# MCU.net
KiCad netlist of a schematic drawn in Altium Designer
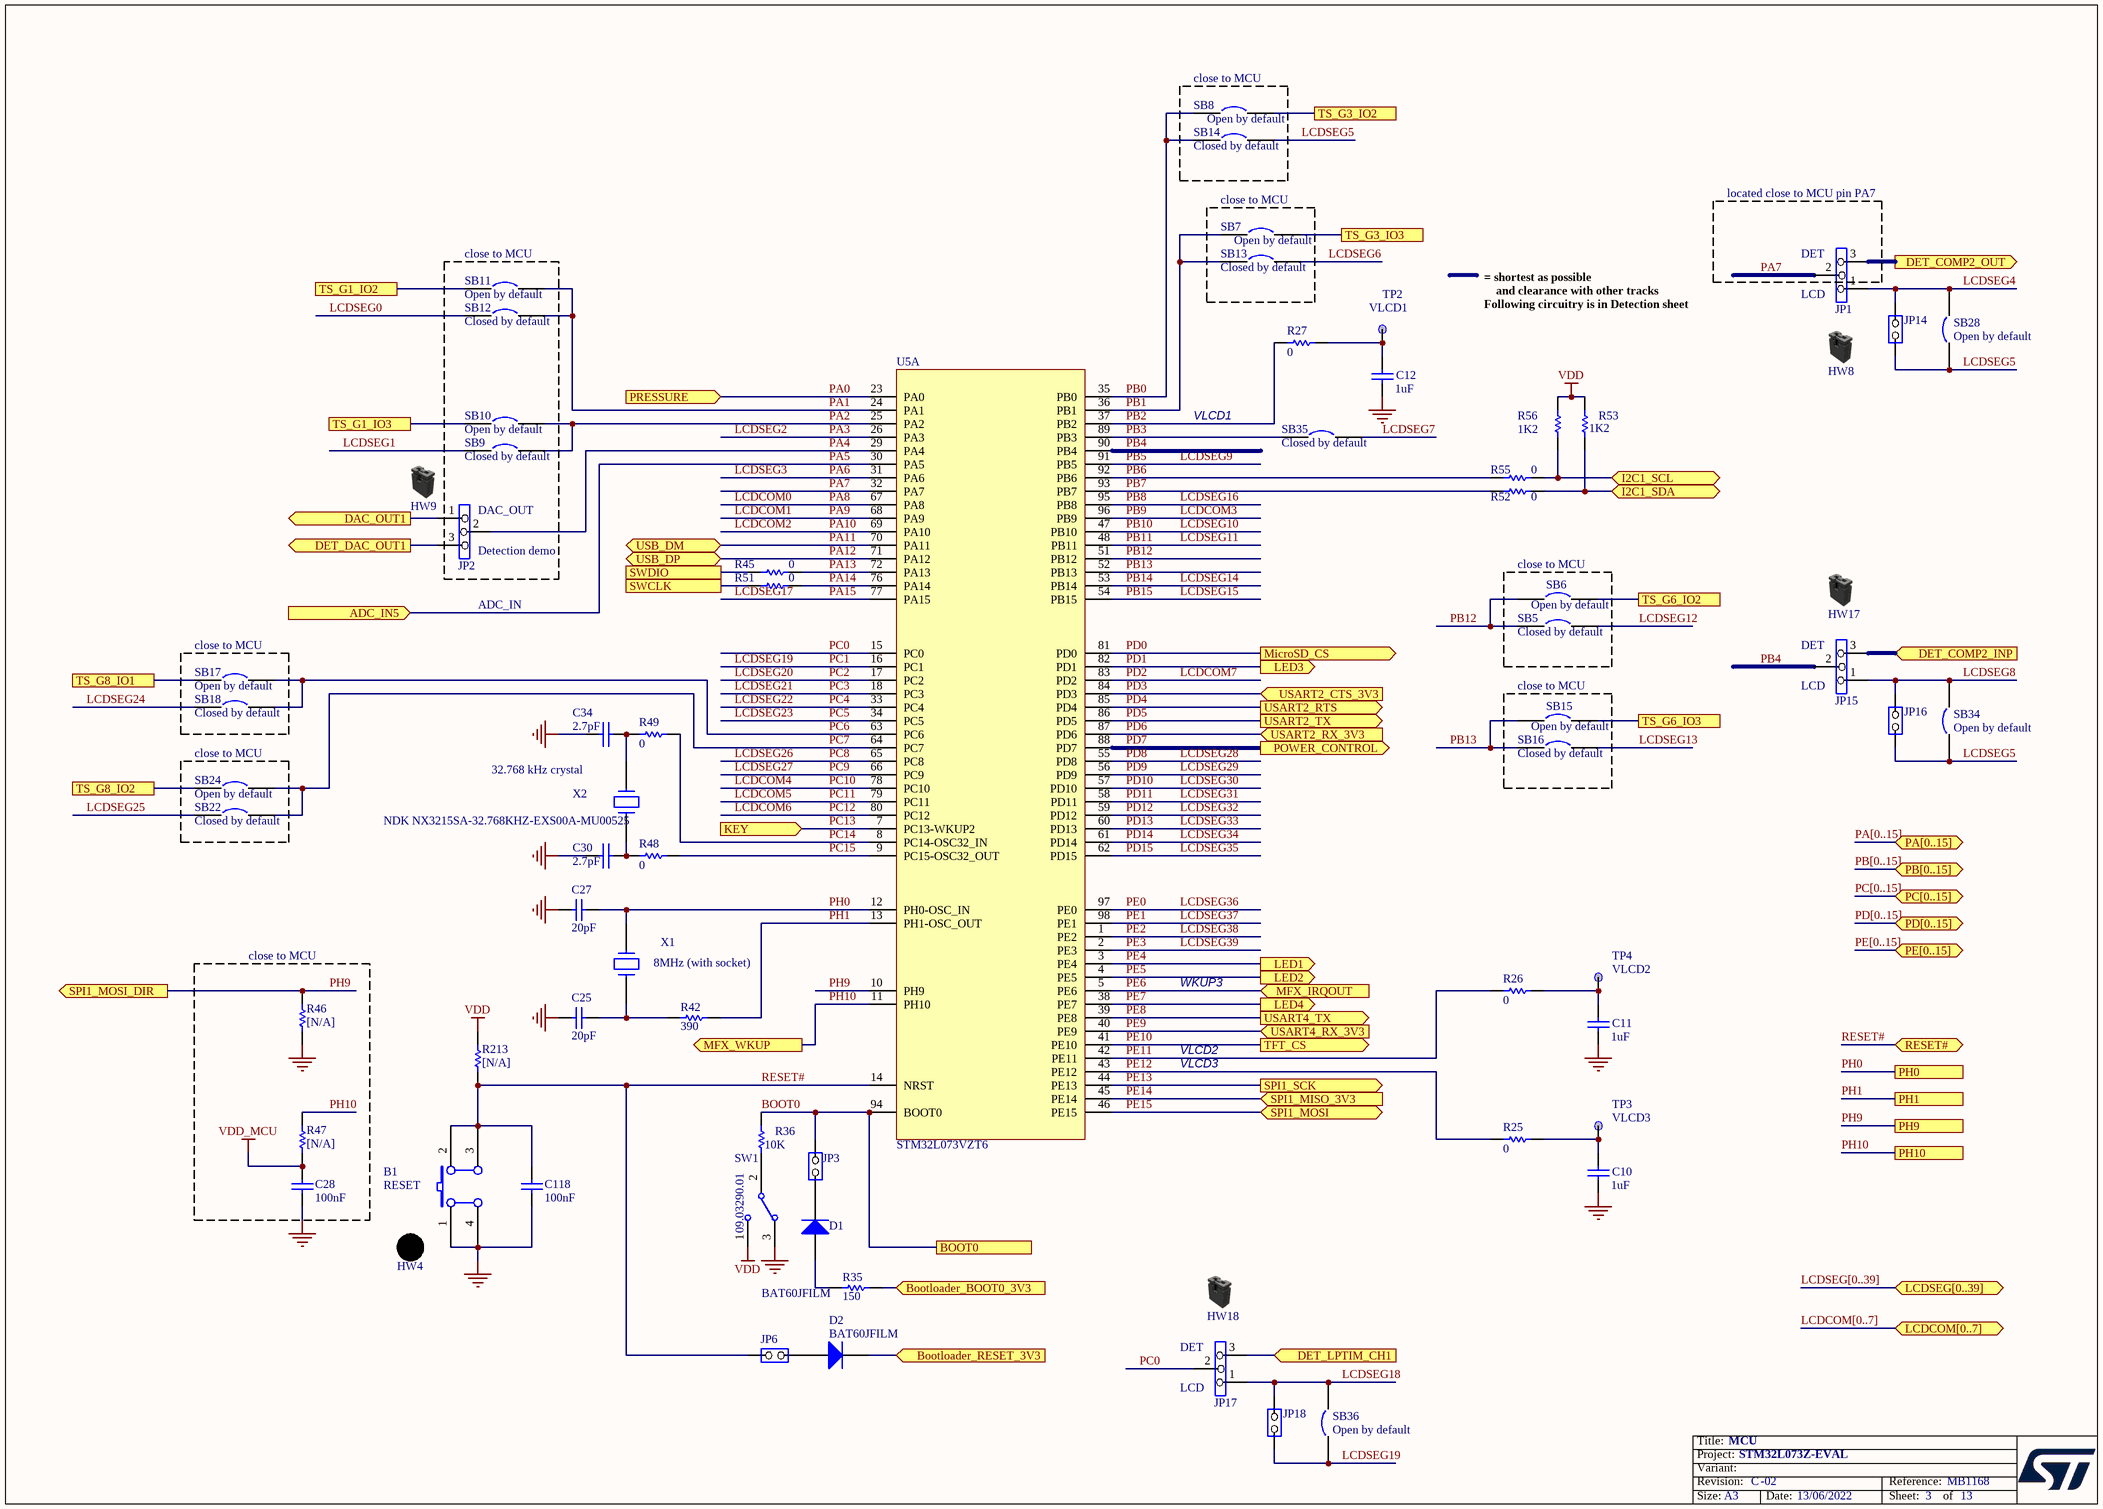
[diagram p0: MCU.SchDoc]

(export (version "E")
  (design (tool "Eeschema 10.0.6"))
  (components
    (comp (ref "B1")
      (value "RESET")
      (footprint "PB10")
      (description "SE PUSHBUTTON")
      (libsource (lib "Documents") (part "SW PUSHBUTTON"))
    )
    (comp (ref "C10")
      (value "1uF")
      (footprint "0603C")
      (description "Capacitor")
      (fields (field (name "PUBLISHER") "Altium Limited"))
      (libsource (lib "Miscellaneous Devices") (part "CAP"))
    )
    (comp (ref "C11")
      (value "1uF")
      (footprint "0603C")
      (description "Capacitor")
      (fields (field (name "PUBLISHER") "Altium Limited"))
      (libsource (lib "Miscellaneous Devices") (part "CAP"))
    )
    (comp (ref "C12")
      (value "1uF")
      (footprint "0603C")
      (description "Capacitor")
      (fields (field (name "PUBLISHER") "Altium Limited"))
      (libsource (lib "Miscellaneous Devices") (part "CAP"))
    )
    (comp (ref "C25")
      (value "20pF")
      (footprint "0402C")
      (description "Capacitor")
      (fields (field (name "PUBLISHER") "Altium Limited"))
      (libsource (lib "Miscellaneous Devices") (part "CAP"))
    )
    (comp (ref "C27")
      (value "20pF")
      (footprint "0402C")
      (description "Capacitor")
      (fields (field (name "PUBLISHER") "Altium Limited"))
      (libsource (lib "Miscellaneous Devices") (part "CAP"))
    )
    (comp (ref "C28")
      (value "100nF")
      (footprint "0402C")
      (description "Capacitor")
      (fields (field (name "PUBLISHER") "Altium Limited"))
      (libsource (lib "Miscellaneous Devices") (part "CAP"))
    )
    (comp (ref "C30")
      (value "2.7pF")
      (footprint "0603C")
      (description "Capacitor")
      (libsource (lib "*") (part "CAP"))
    )
    (comp (ref "C34")
      (value "2.7pF")
      (footprint "0603C")
      (description "Capacitor")
      (libsource (lib "*") (part "CAP"))
    )
    (comp (ref "C118")
      (value "100nF")
      (footprint "0402C")
      (description "Capacitor")
      (fields (field (name "PUBLISHER") "Altium Limited"))
      (libsource (lib "Miscellaneous Devices") (part "CAP"))
    )
    (comp (ref "D1")
      (value "BAT60JFILM")
      (footprint "SOD-323")
      (description "Default Diode")
      (fields (field (name "PUBLISHER") "Altium Limited"))
      (libsource (lib "Miscellaneous Devices") (part "Diode"))
    )
    (comp (ref "D2")
      (value "BAT60JFILM")
      (footprint "SOD-323")
      (description "Default Diode")
      (fields (field (name "PUBLISHER") "Altium Limited"))
      (libsource (lib "Miscellaneous Devices") (part "Diode"))
    )
    (comp (ref "HW4") (value "BUTTON_HAT_BLACK") (libsource (lib "MB1168") (part "BUTTON_HAT_BLACK")))
    (comp (ref "HW8") (value "Shunt Black 2.54mm") (libsource (lib "MB1168") (part "Shunt Black 2.54mm")))
    (comp (ref "HW9") (value "Shunt Black 2.54mm") (libsource (lib "MB1168") (part "Shunt Black 2.54mm")))
    (comp (ref "HW17") (value "Shunt Black 2.54mm") (libsource (lib "MB1168") (part "Shunt Black 2.54mm")))
    (comp (ref "HW18") (value "Shunt Black 2.54mm") (libsource (lib "MB1168") (part "Shunt Black 2.54mm")))
    (comp (ref "JP1") (value "~") (footprint "SIP3") (libsource (lib "STR910_SCHLIB") (part "Jumper3")))
    (comp (ref "JP2") (value "~") (footprint "SIP3") (libsource (lib "STR910_SCHLIB") (part "Jumper3")))
    (comp (ref "JP3") (value "~") (footprint "SIP2") (libsource (lib "*") (part "JP2")))
    (comp (ref "JP6") (value "~") (footprint "SIP2") (libsource (lib "*") (part "JP2")))
    (comp (ref "JP14") (value "~") (footprint "SIP2") (libsource (lib "*") (part "JP2")))
    (comp (ref "JP15") (value "~") (footprint "SIP3") (libsource (lib "STR910_SCHLIB") (part "Jumper3")))
    (comp (ref "JP16") (value "~") (footprint "SIP2") (libsource (lib "*") (part "JP2")))
    (comp (ref "JP17") (value "~") (footprint "SIP3") (libsource (lib "STR910_SCHLIB") (part "Jumper3")))
    (comp (ref "JP18") (value "~") (footprint "SIP2") (libsource (lib "*") (part "JP2")))
    (comp (ref "R25")
      (value "0")
      (footprint "0603R")
      (description "Resistor")
      (fields (field (name "PUBLISHER") "Altium Limited"))
      (libsource (lib "Miscellaneous Devices") (part "Res1"))
    )
    (comp (ref "R26")
      (value "0")
      (footprint "0603R")
      (description "Resistor")
      (fields (field (name "PUBLISHER") "Altium Limited"))
      (libsource (lib "Miscellaneous Devices") (part "Res1"))
    )
    (comp (ref "R27")
      (value "0")
      (footprint "0603R")
      (description "Resistor")
      (fields (field (name "PUBLISHER") "Altium Limited"))
      (libsource (lib "Miscellaneous Devices") (part "Res1"))
    )
    (comp (ref "R35")
      (value "150")
      (footprint "0402R")
      (description "Resistor")
      (fields (field (name "PUBLISHER") "Altium Limited"))
      (libsource (lib "Miscellaneous Devices") (part "res1"))
    )
    (comp (ref "R36")
      (value "10K")
      (footprint "0402R")
      (description "Resistor")
      (fields (field (name "PUBLISHER") "Altium Limited"))
      (libsource (lib "Miscellaneous Devices") (part "res1"))
    )
    (comp (ref "R42")
      (value "390")
      (footprint "0603R")
      (description "Resistor")
      (fields (field (name "PUBLISHER") "Altium Limited"))
      (libsource (lib "Miscellaneous Devices") (part "Res1"))
    )
    (comp (ref "R45")
      (value "0")
      (footprint "0603R")
      (description "Resistor")
      (fields (field (name "PUBLISHER") "Altium Limited"))
      (libsource (lib "Miscellaneous Devices") (part "Res1"))
    )
    (comp (ref "R46")
      (value "[N/A]")
      (footprint "0603R")
      (description "Resistor")
      (fields (field (name "PUBLISHER") "Altium Limited"))
      (libsource (lib "Miscellaneous Devices") (part "res1"))
    )
    (comp (ref "R47")
      (value "[N/A]")
      (footprint "0603R")
      (description "Resistor")
      (fields (field (name "PUBLISHER") "Altium Limited"))
      (libsource (lib "Miscellaneous Devices") (part "res1"))
    )
    (comp (ref "R48")
      (value "0")
      (footprint "0603R")
      (description "Resistor")
      (fields (field (name "PUBLISHER") "Altium Limited"))
      (libsource (lib "") (part "Res1_1"))
    )
    (comp (ref "R49")
      (value "0")
      (footprint "0603R")
      (description "Resistor")
      (fields (field (name "PUBLISHER") "Altium Limited"))
      (libsource (lib "") (part "Res1_1"))
    )
    (comp (ref "R51")
      (value "0")
      (footprint "0603R")
      (description "Resistor")
      (fields (field (name "PUBLISHER") "Altium Limited"))
      (libsource (lib "Miscellaneous Devices") (part "Res1"))
    )
    (comp (ref "R52")
      (value "0")
      (footprint "0603R")
      (description "Resistor")
      (fields (field (name "PUBLISHER") "Altium Limited"))
      (libsource (lib "Miscellaneous Devices") (part "Res1"))
    )
    (comp (ref "R53")
      (value "1K2")
      (footprint "0603R")
      (description "Resistor")
      (fields (field (name "PUBLISHER") "Altium Limited"))
      (libsource (lib "Miscellaneous Devices") (part "Res1"))
    )
    (comp (ref "R55")
      (value "0")
      (footprint "0603R")
      (description "Resistor")
      (fields (field (name "PUBLISHER") "Altium Limited"))
      (libsource (lib "Miscellaneous Devices") (part "Res1"))
    )
    (comp (ref "R56")
      (value "1K2")
      (footprint "0603R")
      (description "Resistor")
      (fields (field (name "PUBLISHER") "Altium Limited"))
      (libsource (lib "Miscellaneous Devices") (part "Res1"))
    )
    (comp (ref "R213")
      (value "[N/A]")
      (footprint "0603R")
      (description "Resistor")
      (fields (field (name "PUBLISHER") "Altium Limited"))
      (libsource (lib "Miscellaneous Devices") (part "res1"))
    )
    (comp (ref "SB5")
      (value "Closed by default")
      (footprint "SB_0603")
      (description "Circuit Breaker")
      (fields (field (name "PUBLISHER") "Altium Limited"))
      (libsource (lib "Miscellaneous Devices") (part "Circuit Breaker"))
    )
    (comp (ref "SB6")
      (value "Open by default")
      (footprint "SB_0603")
      (description "Circuit Breaker")
      (fields (field (name "PUBLISHER") "Altium Limited"))
      (libsource (lib "Miscellaneous Devices") (part "Circuit Breaker"))
    )
    (comp (ref "SB7")
      (value "Open by default")
      (footprint "SB_0603")
      (description "Circuit Breaker")
      (fields (field (name "PUBLISHER") "Altium Limited"))
      (libsource (lib "Miscellaneous Devices") (part "Circuit Breaker"))
    )
    (comp (ref "SB8")
      (value "Open by default")
      (footprint "SB_0603")
      (description "Circuit Breaker")
      (fields (field (name "PUBLISHER") "Altium Limited"))
      (libsource (lib "Miscellaneous Devices") (part "Circuit Breaker"))
    )
    (comp (ref "SB9")
      (value "Closed by default")
      (footprint "SB_0603")
      (description "Circuit Breaker")
      (fields (field (name "PUBLISHER") "Altium Limited"))
      (libsource (lib "Miscellaneous Devices") (part "Circuit Breaker"))
    )
    (comp (ref "SB10")
      (value "Open by default")
      (footprint "SB_0603")
      (description "Circuit Breaker")
      (fields (field (name "PUBLISHER") "Altium Limited"))
      (libsource (lib "Miscellaneous Devices") (part "Circuit Breaker"))
    )
    (comp (ref "SB11")
      (value "Open by default")
      (footprint "SB_0603")
      (description "Circuit Breaker")
      (fields (field (name "PUBLISHER") "Altium Limited"))
      (libsource (lib "Miscellaneous Devices") (part "Circuit Breaker"))
    )
    (comp (ref "SB12")
      (value "Closed by default")
      (footprint "SB_0603")
      (description "Circuit Breaker")
      (fields (field (name "PUBLISHER") "Altium Limited"))
      (libsource (lib "Miscellaneous Devices") (part "Circuit Breaker"))
    )
    (comp (ref "SB13")
      (value "Closed by default")
      (footprint "SB_0603")
      (description "Circuit Breaker")
      (fields (field (name "PUBLISHER") "Altium Limited"))
      (libsource (lib "Miscellaneous Devices") (part "Circuit Breaker"))
    )
    (comp (ref "SB14")
      (value "Closed by default")
      (footprint "SB_0603")
      (description "Circuit Breaker")
      (fields (field (name "PUBLISHER") "Altium Limited"))
      (libsource (lib "Miscellaneous Devices") (part "Circuit Breaker"))
    )
    (comp (ref "SB15")
      (value "Open by default")
      (footprint "SB_0603")
      (description "Circuit Breaker")
      (fields (field (name "PUBLISHER") "Altium Limited"))
      (libsource (lib "Miscellaneous Devices") (part "Circuit Breaker"))
    )
    (comp (ref "SB16")
      (value "Closed by default")
      (footprint "SB_0603")
      (description "Circuit Breaker")
      (fields (field (name "PUBLISHER") "Altium Limited"))
      (libsource (lib "Miscellaneous Devices") (part "Circuit Breaker"))
    )
    (comp (ref "SB17")
      (value "Open by default")
      (footprint "SB_0603")
      (description "Circuit Breaker")
      (fields (field (name "PUBLISHER") "Altium Limited"))
      (libsource (lib "Miscellaneous Devices") (part "Circuit Breaker"))
    )
    (comp (ref "SB18")
      (value "Closed by default")
      (footprint "SB_0603")
      (description "Circuit Breaker")
      (fields (field (name "PUBLISHER") "Altium Limited"))
      (libsource (lib "Miscellaneous Devices") (part "Circuit Breaker"))
    )
    (comp (ref "SB22")
      (value "Closed by default")
      (footprint "SB_0603")
      (description "Circuit Breaker")
      (fields (field (name "PUBLISHER") "Altium Limited"))
      (libsource (lib "Miscellaneous Devices") (part "Circuit Breaker"))
    )
    (comp (ref "SB24")
      (value "Open by default")
      (footprint "SB_0603")
      (description "Circuit Breaker")
      (fields (field (name "PUBLISHER") "Altium Limited"))
      (libsource (lib "Miscellaneous Devices") (part "Circuit Breaker"))
    )
    (comp (ref "SB28")
      (value "Open by default")
      (footprint "SB_0603")
      (description "Circuit Breaker")
      (fields (field (name "PUBLISHER") "Altium Limited"))
      (libsource (lib "Miscellaneous Devices") (part "Circuit Breaker"))
    )
    (comp (ref "SB34")
      (value "Open by default")
      (footprint "SB_0603")
      (description "Circuit Breaker")
      (fields (field (name "PUBLISHER") "Altium Limited"))
      (libsource (lib "Miscellaneous Devices") (part "Circuit Breaker"))
    )
    (comp (ref "SB35")
      (value "Closed by default")
      (footprint "SB_0603")
      (description "Circuit Breaker")
      (fields (field (name "PUBLISHER") "Altium Limited"))
      (libsource (lib "Miscellaneous Devices") (part "Circuit Breaker"))
    )
    (comp (ref "SB36")
      (value "Open by default")
      (footprint "SB_0603")
      (description "Circuit Breaker")
      (fields (field (name "PUBLISHER") "Altium Limited"))
      (libsource (lib "Miscellaneous Devices") (part "Circuit Breaker"))
    )
    (comp (ref "SW1")
      (value "09.03290.01")
      (footprint "SW1_3TH_2R54_10X2R5")
      (description "SPDT Subminiature Toggle Switch, Right Angle Mounting, Vertical Actuation")
      (fields (field (name "PUBLISHER") "Altium Limited"))
      (libsource (lib "Miscellaneous Devices") (part "SW-SPDT"))
    )
    (comp (ref "TP2")
      (value "TP")
      (footprint "TP")
      (fields (field (name "SILKSCREEN") "VLCD1"))
      (libsource (lib "*") (part "TP"))
    )
    (comp (ref "TP3")
      (value "TP")
      (footprint "TP")
      (fields (field (name "SILKSCREEN") "VLCD3"))
      (libsource (lib "*") (part "TP"))
    )
    (comp (ref "TP4")
      (value "TP")
      (footprint "TP")
      (fields (field (name "SILKSCREEN") "VLCD2"))
      (libsource (lib "*") (part "TP"))
    )
    (comp (ref "U5")
      (value "STM32L073VZT6")
      (footprint "IC149_100_025_B5")
      (libsource (lib "Almos") (part "BigNemo"))
    )
    (comp (ref "X1")
      (value "8MHz (with socket)")
      (footprint "XTAL_SOCKET")
      (description "Crystal")
      (libsource (lib "*") (part "CRYSTAL"))
    )
    (comp (ref "X2")
      (value "NDK NX3215SA-32.768KHZ-EXS00A-MU00525")
      (footprint "XTAL_2SM_3R2X1R5")
      (description "Crystal")
      (libsource (lib "MB1167") (part "CRYSTAL_32K"))
    )
  )
  (nets
    (net (code "1") (name "/BOOT0") (class "Default")
      (node (ref "JP3") (pin "1") (pinfunction "COMMON_1") (pintype "passive"))
      (node (ref "R36") (pin "1") (pinfunction "1_1") (pintype "passive"))
      (node (ref "U5") (pin "94") (pinfunction "BOOT0_94") (pintype "passive"))
    )
    (net (code "2") (name "/Bootloader_BOOT0_3V3") (class "Default")
      (node (ref "R35") (pin "2") (pinfunction "2_2") (pintype "passive"))
    )
    (net (code "3") (name "/Bootloader_RESET_3V3") (class "Default")
      (node (ref "D2") (pin "2") (pinfunction "K_2") (pintype "passive"))
    )
    (net (code "4") (name "/DAC_OUT1") (class "Default") (node (ref "JP2") (pin "1") (pintype "passive")))
    (net (code "5") (name "/DET_COMP2_INP") (class "Default")
      (node (ref "JP15") (pin "3") (pintype "passive"))
    )
    (net (code "6") (name "/DET_COMP2_OUT") (class "Default")
      (node (ref "JP1") (pin "3") (pintype "passive"))
    )
    (net (code "7") (name "/DET_DAC_OUT1") (class "Default") (node (ref "JP2") (pin "3") (pintype "passive")))
    (net (code "8") (name "/DET_LPTIM_CH1") (class "Default")
      (node (ref "JP17") (pin "3") (pintype "passive"))
    )
    (net (code "9") (name "/I2C1_SCL") (class "Default")
      (node (ref "R55") (pin "2") (pinfunction "2_2") (pintype "passive"))
      (node (ref "R56") (pin "1") (pinfunction "1_1") (pintype "passive"))
    )
    (net (code "10") (name "/I2C1_SDA") (class "Default")
      (node (ref "R52") (pin "2") (pinfunction "2_2") (pintype "passive"))
      (node (ref "R53") (pin "1") (pinfunction "1_1") (pintype "passive"))
    )
    (net (code "11") (name "/LCDCOM0") (class "Default")
      (node (ref "U5") (pin "67") (pinfunction "PA8_67") (pintype "passive"))
    )
    (net (code "12") (name "/LCDCOM1") (class "Default")
      (node (ref "U5") (pin "68") (pinfunction "PA9_68") (pintype "passive"))
    )
    (net (code "13") (name "/LCDCOM2") (class "Default")
      (node (ref "U5") (pin "69") (pinfunction "PA10_69") (pintype "passive"))
    )
    (net (code "14") (name "/LCDCOM3") (class "Default")
      (node (ref "U5") (pin "96") (pinfunction "PB9_96") (pintype "passive"))
    )
    (net (code "15") (name "/LCDCOM4") (class "Default")
      (node (ref "U5") (pin "78") (pinfunction "PC10_78") (pintype "passive"))
    )
    (net (code "16") (name "/LCDCOM5") (class "Default")
      (node (ref "U5") (pin "79") (pinfunction "PC11_79") (pintype "passive"))
    )
    (net (code "17") (name "/LCDCOM6") (class "Default")
      (node (ref "U5") (pin "80") (pinfunction "PC12_80") (pintype "passive"))
    )
    (net (code "18") (name "/LCDCOM7") (class "Default")
      (node (ref "U5") (pin "83") (pinfunction "PD2_83") (pintype "passive"))
    )
    (net (code "20") (name "/LCDSEG0") (class "Default")
      (node (ref "SB12") (pin "1") (pinfunction "1_1") (pintype "passive"))
    )
    (net (code "21") (name "/LCDSEG1") (class "Default")
      (node (ref "SB9") (pin "1") (pinfunction "1_1") (pintype "passive"))
    )
    (net (code "22") (name "/LCDSEG2") (class "Default")
      (node (ref "U5") (pin "26") (pinfunction "PA3_26") (pintype "passive"))
    )
    (net (code "23") (name "/LCDSEG3") (class "Default")
      (node (ref "U5") (pin "31") (pinfunction "PA6_31") (pintype "passive"))
    )
    (net (code "24") (name "/LCDSEG4") (class "Default")
      (node (ref "JP1") (pin "1") (pintype "passive"))
      (node (ref "JP14") (pin "2") (pinfunction "NO_2") (pintype "passive"))
      (node (ref "SB28") (pin "2") (pinfunction "2_2") (pintype "passive"))
    )
    (net (code "25") (name "/LCDSEG5") (class "Default")
      (node (ref "JP14") (pin "1") (pinfunction "COMMON_1") (pintype "passive"))
      (node (ref "JP16") (pin "1") (pinfunction "COMMON_1") (pintype "passive"))
      (node (ref "SB14") (pin "2") (pinfunction "2_2") (pintype "passive"))
      (node (ref "SB28") (pin "1") (pinfunction "1_1") (pintype "passive"))
      (node (ref "SB34") (pin "1") (pinfunction "1_1") (pintype "passive"))
    )
    (net (code "26") (name "/LCDSEG6") (class "Default")
      (node (ref "SB13") (pin "2") (pinfunction "2_2") (pintype "passive"))
    )
    (net (code "27") (name "/LCDSEG7") (class "Default")
      (node (ref "SB35") (pin "2") (pinfunction "2_2") (pintype "passive"))
    )
    (net (code "28") (name "/LCDSEG8") (class "Default")
      (node (ref "JP15") (pin "1") (pintype "passive"))
      (node (ref "JP16") (pin "2") (pinfunction "NO_2") (pintype "passive"))
      (node (ref "SB34") (pin "2") (pinfunction "2_2") (pintype "passive"))
    )
    (net (code "29") (name "/LCDSEG9") (class "Default")
      (node (ref "U5") (pin "91") (pinfunction "PB5_91") (pintype "passive"))
    )
    (net (code "30") (name "/LCDSEG10") (class "Default")
      (node (ref "U5") (pin "47") (pinfunction "PB10_47") (pintype "passive"))
    )
    (net (code "31") (name "/LCDSEG11") (class "Default")
      (node (ref "U5") (pin "48") (pinfunction "PB11_48") (pintype "passive"))
    )
    (net (code "32") (name "/LCDSEG12") (class "Default")
      (node (ref "SB5") (pin "2") (pinfunction "2_2") (pintype "passive"))
    )
    (net (code "33") (name "/LCDSEG13") (class "Default")
      (node (ref "SB16") (pin "2") (pinfunction "2_2") (pintype "passive"))
    )
    (net (code "34") (name "/LCDSEG14") (class "Default")
      (node (ref "U5") (pin "53") (pinfunction "PB14_53") (pintype "passive"))
    )
    (net (code "35") (name "/LCDSEG15") (class "Default")
      (node (ref "U5") (pin "54") (pinfunction "PB15_54") (pintype "passive"))
    )
    (net (code "36") (name "/LCDSEG16") (class "Default")
      (node (ref "U5") (pin "95") (pinfunction "PB8_95") (pintype "passive"))
    )
    (net (code "37") (name "/LCDSEG17") (class "Default")
      (node (ref "U5") (pin "77") (pinfunction "PA15_77") (pintype "passive"))
    )
    (net (code "38") (name "/LCDSEG18") (class "Default")
      (node (ref "JP17") (pin "1") (pintype "passive"))
      (node (ref "JP18") (pin "2") (pinfunction "NO_2") (pintype "passive"))
      (node (ref "SB36") (pin "2") (pinfunction "2_2") (pintype "passive"))
    )
    (net (code "39") (name "/LCDSEG19") (class "Default")
      (node (ref "JP18") (pin "1") (pinfunction "COMMON_1") (pintype "passive"))
      (node (ref "SB36") (pin "1") (pinfunction "1_1") (pintype "passive"))
      (node (ref "U5") (pin "16") (pinfunction "PC1_16") (pintype "passive"))
    )
    (net (code "40") (name "/LCDSEG20") (class "Default")
      (node (ref "U5") (pin "17") (pinfunction "PC2_17") (pintype "passive"))
    )
    (net (code "41") (name "/LCDSEG21") (class "Default")
      (node (ref "U5") (pin "18") (pinfunction "PC3_18") (pintype "passive"))
    )
    (net (code "42") (name "/LCDSEG22") (class "Default")
      (node (ref "U5") (pin "33") (pinfunction "PC4_33") (pintype "passive"))
    )
    (net (code "43") (name "/LCDSEG23") (class "Default")
      (node (ref "U5") (pin "34") (pinfunction "PC5_34") (pintype "passive"))
    )
    (net (code "44") (name "/LCDSEG24") (class "Default")
      (node (ref "SB18") (pin "1") (pinfunction "1_1") (pintype "passive"))
    )
    (net (code "45") (name "/LCDSEG25") (class "Default")
      (node (ref "SB22") (pin "1") (pinfunction "1_1") (pintype "passive"))
    )
    (net (code "46") (name "/LCDSEG26") (class "Default")
      (node (ref "U5") (pin "65") (pinfunction "PC8_65") (pintype "passive"))
    )
    (net (code "47") (name "/LCDSEG27") (class "Default")
      (node (ref "U5") (pin "66") (pinfunction "PC9_66") (pintype "passive"))
    )
    (net (code "48") (name "/LCDSEG28") (class "Default")
      (node (ref "U5") (pin "55") (pinfunction "PD8_55") (pintype "passive"))
    )
    (net (code "49") (name "/LCDSEG29") (class "Default")
      (node (ref "U5") (pin "56") (pinfunction "PD9_56") (pintype "passive"))
    )
    (net (code "50") (name "/LCDSEG30") (class "Default")
      (node (ref "U5") (pin "57") (pinfunction "PD10_57") (pintype "passive"))
    )
    (net (code "51") (name "/LCDSEG31") (class "Default")
      (node (ref "U5") (pin "58") (pinfunction "PD11_58") (pintype "passive"))
    )
    (net (code "52") (name "/LCDSEG32") (class "Default")
      (node (ref "U5") (pin "59") (pinfunction "PD12_59") (pintype "passive"))
    )
    (net (code "53") (name "/LCDSEG33") (class "Default")
      (node (ref "U5") (pin "60") (pinfunction "PD13_60") (pintype "passive"))
    )
    (net (code "54") (name "/LCDSEG34") (class "Default")
      (node (ref "U5") (pin "61") (pinfunction "PD14_61") (pintype "passive"))
    )
    (net (code "55") (name "/LCDSEG35") (class "Default")
      (node (ref "U5") (pin "62") (pinfunction "PD15_62") (pintype "passive"))
    )
    (net (code "56") (name "/LCDSEG36") (class "Default")
      (node (ref "U5") (pin "97") (pinfunction "PE0_97") (pintype "passive"))
    )
    (net (code "57") (name "/LCDSEG37") (class "Default")
      (node (ref "U5") (pin "98") (pinfunction "PE1_98") (pintype "passive"))
    )
    (net (code "58") (name "/LCDSEG38") (class "Default")
      (node (ref "U5") (pin "1") (pinfunction "PE2_1") (pintype "passive"))
    )
    (net (code "59") (name "/LCDSEG39") (class "Default")
      (node (ref "U5") (pin "2") (pinfunction "PE3_2") (pintype "passive"))
    )
    (net (code "61") (name "/PA0") (class "Default")
      (node (ref "U5") (pin "23") (pinfunction "PA0_23") (pintype "passive"))
    )
    (net (code "62") (name "/PA1") (class "Default")
      (node (ref "SB11") (pin "2") (pinfunction "2_2") (pintype "passive"))
      (node (ref "SB12") (pin "2") (pinfunction "2_2") (pintype "passive"))
      (node (ref "U5") (pin "24") (pinfunction "PA1_24") (pintype "passive"))
    )
    (net (code "63") (name "/PA2") (class "Default")
      (node (ref "SB10") (pin "2") (pinfunction "2_2") (pintype "passive"))
      (node (ref "SB9") (pin "2") (pinfunction "2_2") (pintype "passive"))
      (node (ref "U5") (pin "25") (pinfunction "PA2_25") (pintype "passive"))
    )
    (net (code "64") (name "/PA4") (class "Default")
      (node (ref "JP2") (pin "2") (pintype "passive"))
      (node (ref "U5") (pin "29") (pinfunction "PA4_29") (pintype "passive"))
    )
    (net (code "65") (name "/PA5") (class "Default")
      (node (ref "U5") (pin "30") (pinfunction "PA5_30") (pintype "passive"))
    )
    (net (code "66") (name "/PA7") (class "Default")
      (node (ref "JP1") (pin "2") (pintype "passive"))
      (node (ref "U5") (pin "32") (pinfunction "PA7_32") (pintype "passive"))
    )
    (net (code "67") (name "/PA11") (class "Default")
      (node (ref "U5") (pin "70") (pinfunction "PA11_70") (pintype "passive"))
    )
    (net (code "68") (name "/PA12") (class "Default")
      (node (ref "U5") (pin "71") (pinfunction "PA12_71") (pintype "passive"))
    )
    (net (code "69") (name "/PA13") (class "Default")
      (node (ref "R45") (pin "2") (pinfunction "2_2") (pintype "passive"))
      (node (ref "U5") (pin "72") (pinfunction "PA13_72") (pintype "passive"))
    )
    (net (code "70") (name "/PA14") (class "Default")
      (node (ref "R51") (pin "2") (pinfunction "2_2") (pintype "passive"))
      (node (ref "U5") (pin "76") (pinfunction "PA14_76") (pintype "passive"))
    )
    (net (code "72") (name "/PB0") (class "Default")
      (node (ref "SB14") (pin "1") (pinfunction "1_1") (pintype "passive"))
      (node (ref "SB8") (pin "1") (pinfunction "1_1") (pintype "passive"))
      (node (ref "U5") (pin "35") (pinfunction "PB0_35") (pintype "passive"))
    )
    (net (code "73") (name "/PB1") (class "Default")
      (node (ref "SB13") (pin "1") (pinfunction "1_1") (pintype "passive"))
      (node (ref "SB7") (pin "1") (pinfunction "1_1") (pintype "passive"))
      (node (ref "U5") (pin "36") (pinfunction "PB1_36") (pintype "passive"))
    )
    (net (code "74") (name "/PB2") (class "Default")
      (node (ref "R27") (pin "1") (pinfunction "1_1") (pintype "passive"))
      (node (ref "U5") (pin "37") (pinfunction "PB2_37") (pintype "passive"))
    )
    (net (code "75") (name "/PB3") (class "Default")
      (node (ref "SB35") (pin "1") (pinfunction "1_1") (pintype "passive"))
      (node (ref "U5") (pin "89") (pinfunction "PB3_89") (pintype "passive"))
    )
    (net (code "76") (name "/PB4") (class "Default")
      (node (ref "JP15") (pin "2") (pintype "passive"))
      (node (ref "U5") (pin "90") (pinfunction "PB4_90") (pintype "passive"))
    )
    (net (code "77") (name "/PB6") (class "Default")
      (node (ref "R55") (pin "1") (pinfunction "1_1") (pintype "passive"))
      (node (ref "U5") (pin "92") (pinfunction "PB6_92") (pintype "passive"))
    )
    (net (code "78") (name "/PB7") (class "Default")
      (node (ref "R52") (pin "1") (pinfunction "1_1") (pintype "passive"))
      (node (ref "U5") (pin "93") (pinfunction "PB7_93") (pintype "passive"))
    )
    (net (code "79") (name "/PB12") (class "Default")
      (node (ref "SB5") (pin "1") (pinfunction "1_1") (pintype "passive"))
      (node (ref "SB6") (pin "1") (pinfunction "1_1") (pintype "passive"))
      (node (ref "U5") (pin "51") (pinfunction "PB12_51") (pintype "passive"))
    )
    (net (code "80") (name "/PB13") (class "Default")
      (node (ref "SB15") (pin "1") (pinfunction "1_1") (pintype "passive"))
      (node (ref "SB16") (pin "1") (pinfunction "1_1") (pintype "passive"))
      (node (ref "U5") (pin "52") (pinfunction "PB13_52") (pintype "passive"))
    )
    (net (code "82") (name "/PC0") (class "Default")
      (node (ref "JP17") (pin "2") (pintype "passive"))
      (node (ref "U5") (pin "15") (pinfunction "PC0_15") (pintype "passive"))
    )
    (net (code "83") (name "/PC6") (class "Default")
      (node (ref "SB17") (pin "2") (pinfunction "2_2") (pintype "passive"))
      (node (ref "SB18") (pin "2") (pinfunction "2_2") (pintype "passive"))
      (node (ref "U5") (pin "63") (pinfunction "PC6_63") (pintype "passive"))
    )
    (net (code "84") (name "/PC7") (class "Default")
      (node (ref "SB22") (pin "2") (pinfunction "2_2") (pintype "passive"))
      (node (ref "SB24") (pin "2") (pinfunction "2_2") (pintype "passive"))
      (node (ref "U5") (pin "64") (pinfunction "PC7_64") (pintype "passive"))
    )
    (net (code "85") (name "/PC13") (class "Default")
      (node (ref "U5") (pin "7") (pinfunction "PC13-WKUP2_7") (pintype "passive"))
    )
    (net (code "86") (name "/PC14") (class "Default")
      (node (ref "R49") (pin "2") (pinfunction "2_2") (pintype "passive"))
      (node (ref "U5") (pin "8") (pinfunction "PC14-OSC32_IN_8") (pintype "passive"))
    )
    (net (code "87") (name "/PC15") (class "Default")
      (node (ref "R48") (pin "2") (pinfunction "2_2") (pintype "passive"))
      (node (ref "U5") (pin "9") (pinfunction "PC15-OSC32_OUT_9") (pintype "passive"))
    )
    (net (code "89") (name "/PD0") (class "Default")
      (node (ref "U5") (pin "81") (pinfunction "PD0_81") (pintype "passive"))
    )
    (net (code "90") (name "/PD1") (class "Default")
      (node (ref "U5") (pin "82") (pinfunction "PD1_82") (pintype "passive"))
    )
    (net (code "91") (name "/PD3") (class "Default")
      (node (ref "U5") (pin "84") (pinfunction "PD3_84") (pintype "passive"))
    )
    (net (code "92") (name "/PD4") (class "Default")
      (node (ref "U5") (pin "85") (pinfunction "PD4_85") (pintype "passive"))
    )
    (net (code "93") (name "/PD5") (class "Default")
      (node (ref "U5") (pin "86") (pinfunction "PD5_86") (pintype "passive"))
    )
    (net (code "94") (name "/PD6") (class "Default")
      (node (ref "U5") (pin "87") (pinfunction "PD6_87") (pintype "passive"))
    )
    (net (code "95") (name "/PD7") (class "Default")
      (node (ref "U5") (pin "88") (pinfunction "PD7_88") (pintype "passive"))
    )
    (net (code "97") (name "/PE4") (class "Default")
      (node (ref "U5") (pin "3") (pinfunction "PE4_3") (pintype "passive"))
    )
    (net (code "98") (name "/PE5") (class "Default")
      (node (ref "U5") (pin "4") (pinfunction "PE5_4") (pintype "passive"))
    )
    (net (code "99") (name "/PE6") (class "Default")
      (node (ref "U5") (pin "5") (pinfunction "PE6_5") (pintype "passive"))
    )
    (net (code "100") (name "/PE7") (class "Default")
      (node (ref "U5") (pin "38") (pinfunction "PE7_38") (pintype "passive"))
    )
    (net (code "101") (name "/PE8") (class "Default")
      (node (ref "U5") (pin "39") (pinfunction "PE8_39") (pintype "passive"))
    )
    (net (code "102") (name "/PE9") (class "Default")
      (node (ref "U5") (pin "40") (pinfunction "PE9_40") (pintype "passive"))
    )
    (net (code "103") (name "/PE10") (class "Default")
      (node (ref "U5") (pin "41") (pinfunction "PE10_41") (pintype "passive"))
    )
    (net (code "104") (name "/PE11") (class "Default")
      (node (ref "R26") (pin "1") (pinfunction "1_1") (pintype "passive"))
      (node (ref "U5") (pin "42") (pinfunction "PE11_42") (pintype "passive"))
    )
    (net (code "105") (name "/PE12") (class "Default")
      (node (ref "R25") (pin "1") (pinfunction "1_1") (pintype "passive"))
      (node (ref "U5") (pin "43") (pinfunction "PE12_43") (pintype "passive"))
    )
    (net (code "106") (name "/PE13") (class "Default")
      (node (ref "U5") (pin "44") (pinfunction "PE13_44") (pintype "passive"))
    )
    (net (code "107") (name "/PE14") (class "Default")
      (node (ref "U5") (pin "45") (pinfunction "PE14_45") (pintype "passive"))
    )
    (net (code "108") (name "/PE15") (class "Default")
      (node (ref "U5") (pin "46") (pinfunction "PE15_46") (pintype "passive"))
    )
    (net (code "110") (name "/PH0") (class "Default")
      (node (ref "C27") (pin "1") (pinfunction "1_1") (pintype "passive"))
      (node (ref "U5") (pin "12") (pinfunction "PH0-OSC_IN_12") (pintype "passive"))
      (node (ref "X1") (pin "2") (pinfunction "2_2") (pintype "passive"))
    )
    (net (code "111") (name "/PH1") (class "Default")
      (node (ref "R42") (pin "1") (pinfunction "1_1") (pintype "passive"))
      (node (ref "U5") (pin "13") (pinfunction "PH1-OSC_OUT_13") (pintype "passive"))
    )
    (net (code "112") (name "/PH9") (class "Default")
      (node (ref "R46") (pin "2") (pinfunction "2_2") (pintype "passive"))
      (node (ref "U5") (pin "10") (pinfunction "PH9_10") (pintype "passive"))
    )
    (net (code "113") (name "/PH10") (class "Default")
      (node (ref "R47") (pin "2") (pinfunction "2_2") (pintype "passive"))
      (node (ref "U5") (pin "11") (pinfunction "PH10_11") (pintype "passive"))
    )
    (net (code "114") (name "/RESET#") (class "Default")
      (node (ref "B1") (pin "2") (pinfunction "B0_2") (pintype "passive"))
      (node (ref "B1") (pin "3") (pinfunction "B1_3") (pintype "passive"))
      (node (ref "C118") (pin "2") (pinfunction "2_2") (pintype "passive"))
      (node (ref "JP6") (pin "1") (pinfunction "COMMON_1") (pintype "passive"))
      (node (ref "R213") (pin "1") (pinfunction "1_1") (pintype "passive"))
      (node (ref "U5") (pin "14") (pinfunction "NRST_14") (pintype "passive"))
    )
    (net (code "115") (name "/SWCLK") (class "Default")
      (node (ref "R51") (pin "1") (pinfunction "1_1") (pintype "passive"))
    )
    (net (code "116") (name "/SWDIO") (class "Default")
      (node (ref "R45") (pin "1") (pinfunction "1_1") (pintype "passive"))
    )
    (net (code "117") (name "/TS_G1_IO2") (class "Default")
      (node (ref "SB11") (pin "1") (pinfunction "1_1") (pintype "passive"))
    )
    (net (code "118") (name "/TS_G1_IO3") (class "Default")
      (node (ref "SB10") (pin "1") (pinfunction "1_1") (pintype "passive"))
    )
    (net (code "119") (name "/TS_G3_IO2") (class "Default")
      (node (ref "SB8") (pin "2") (pinfunction "2_2") (pintype "passive"))
    )
    (net (code "120") (name "/TS_G3_IO3") (class "Default")
      (node (ref "SB7") (pin "2") (pinfunction "2_2") (pintype "passive"))
    )
    (net (code "121") (name "/TS_G6_IO2") (class "Default")
      (node (ref "SB6") (pin "2") (pinfunction "2_2") (pintype "passive"))
    )
    (net (code "122") (name "/TS_G6_IO3") (class "Default")
      (node (ref "SB15") (pin "2") (pinfunction "2_2") (pintype "passive"))
    )
    (net (code "123") (name "/TS_G8_IO1") (class "Default")
      (node (ref "SB17") (pin "1") (pinfunction "1_1") (pintype "passive"))
    )
    (net (code "124") (name "/TS_G8_IO2") (class "Default")
      (node (ref "SB24") (pin "1") (pinfunction "1_1") (pintype "passive"))
    )
    (net (code "125") (name "GND") (class "Default")
      (node (ref "B1") (pin "1") (pinfunction "A0_1") (pintype "passive"))
      (node (ref "B1") (pin "4") (pinfunction "A1_4") (pintype "passive"))
      (node (ref "C10") (pin "1") (pinfunction "1_1") (pintype "passive"))
      (node (ref "C11") (pin "1") (pinfunction "1_1") (pintype "passive"))
      (node (ref "C118") (pin "1") (pinfunction "1_1") (pintype "passive"))
      (node (ref "C12") (pin "1") (pinfunction "1_1") (pintype "passive"))
      (node (ref "C25") (pin "2") (pinfunction "2_2") (pintype "passive"))
      (node (ref "C27") (pin "2") (pinfunction "2_2") (pintype "passive"))
      (node (ref "C28") (pin "1") (pinfunction "1_1") (pintype "passive"))
      (node (ref "C30") (pin "2") (pinfunction "2_2") (pintype "passive"))
      (node (ref "C34") (pin "2") (pinfunction "2_2") (pintype "passive"))
      (node (ref "R46") (pin "1") (pinfunction "1_1") (pintype "passive"))
      (node (ref "SW1") (pin "3") (pintype "passive"))
    )
    (net (code "126") (name "Net-(C10-Pad2)") (class "Default")
      (node (ref "C10") (pin "2") (pinfunction "2_2") (pintype "passive"))
      (node (ref "R25") (pin "2") (pinfunction "2_2") (pintype "passive"))
      (node (ref "TP3") (pin "1") (pinfunction "1_1") (pintype "passive"))
    )
    (net (code "127") (name "Net-(C11-Pad2)") (class "Default")
      (node (ref "C11") (pin "2") (pinfunction "2_2") (pintype "passive"))
      (node (ref "R26") (pin "2") (pinfunction "2_2") (pintype "passive"))
      (node (ref "TP4") (pin "1") (pinfunction "1_1") (pintype "passive"))
    )
    (net (code "128") (name "Net-(C12-Pad2)") (class "Default")
      (node (ref "C12") (pin "2") (pinfunction "2_2") (pintype "passive"))
      (node (ref "R27") (pin "2") (pinfunction "2_2") (pintype "passive"))
      (node (ref "TP2") (pin "1") (pinfunction "1_1") (pintype "passive"))
    )
    (net (code "129") (name "Net-(C25-Pad1)") (class "Default")
      (node (ref "C25") (pin "1") (pinfunction "1_1") (pintype "passive"))
      (node (ref "R42") (pin "2") (pinfunction "2_2") (pintype "passive"))
      (node (ref "X1") (pin "1") (pinfunction "1_1") (pintype "passive"))
    )
    (net (code "130") (name "Net-(C30-Pad1)") (class "Default")
      (node (ref "C30") (pin "1") (pinfunction "1_1") (pintype "passive"))
      (node (ref "R48") (pin "1") (pinfunction "1_1") (pintype "passive"))
      (node (ref "X2") (pin "1") (pinfunction "1_1") (pintype "passive"))
    )
    (net (code "131") (name "Net-(C34-Pad1)") (class "Default")
      (node (ref "C34") (pin "1") (pinfunction "1_1") (pintype "passive"))
      (node (ref "R49") (pin "1") (pinfunction "1_1") (pintype "passive"))
      (node (ref "X2") (pin "2") (pinfunction "2_2") (pintype "passive"))
    )
    (net (code "132") (name "Net-(D1-A)") (class "Default")
      (node (ref "D1") (pin "1") (pinfunction "A_1") (pintype "passive"))
      (node (ref "R35") (pin "1") (pinfunction "1_1") (pintype "passive"))
    )
    (net (code "133") (name "Net-(D1-K)") (class "Default")
      (node (ref "D1") (pin "2") (pinfunction "K_2") (pintype "passive"))
      (node (ref "JP3") (pin "2") (pinfunction "NO_2") (pintype "passive"))
    )
    (net (code "134") (name "Net-(D2-A)") (class "Default")
      (node (ref "D2") (pin "1") (pinfunction "A_1") (pintype "passive"))
      (node (ref "JP6") (pin "2") (pinfunction "NO_2") (pintype "passive"))
    )
    (net (code "135") (name "Net-(R36-Pad2)") (class "Default")
      (node (ref "R36") (pin "2") (pinfunction "2_2") (pintype "passive"))
      (node (ref "SW1") (pin "2") (pintype "passive"))
    )
    (net (code "136") (name "VDD") (class "Default")
      (node (ref "R213") (pin "2") (pinfunction "2_2") (pintype "passive"))
      (node (ref "R53") (pin "2") (pinfunction "2_2") (pintype "passive"))
      (node (ref "R56") (pin "2") (pinfunction "2_2") (pintype "passive"))
      (node (ref "SW1") (pin "1") (pintype "passive"))
    )
    (net (code "137") (name "VDD_MCU") (class "Default")
      (node (ref "C28") (pin "2") (pinfunction "2_2") (pintype "passive"))
      (node (ref "R47") (pin "1") (pinfunction "1_1") (pintype "passive"))
    )
  )
)
